# efm8ub1-kalypso-mezzanine-usb-interface-.net
KiCad netlist of a schematic drawn in EAGLE
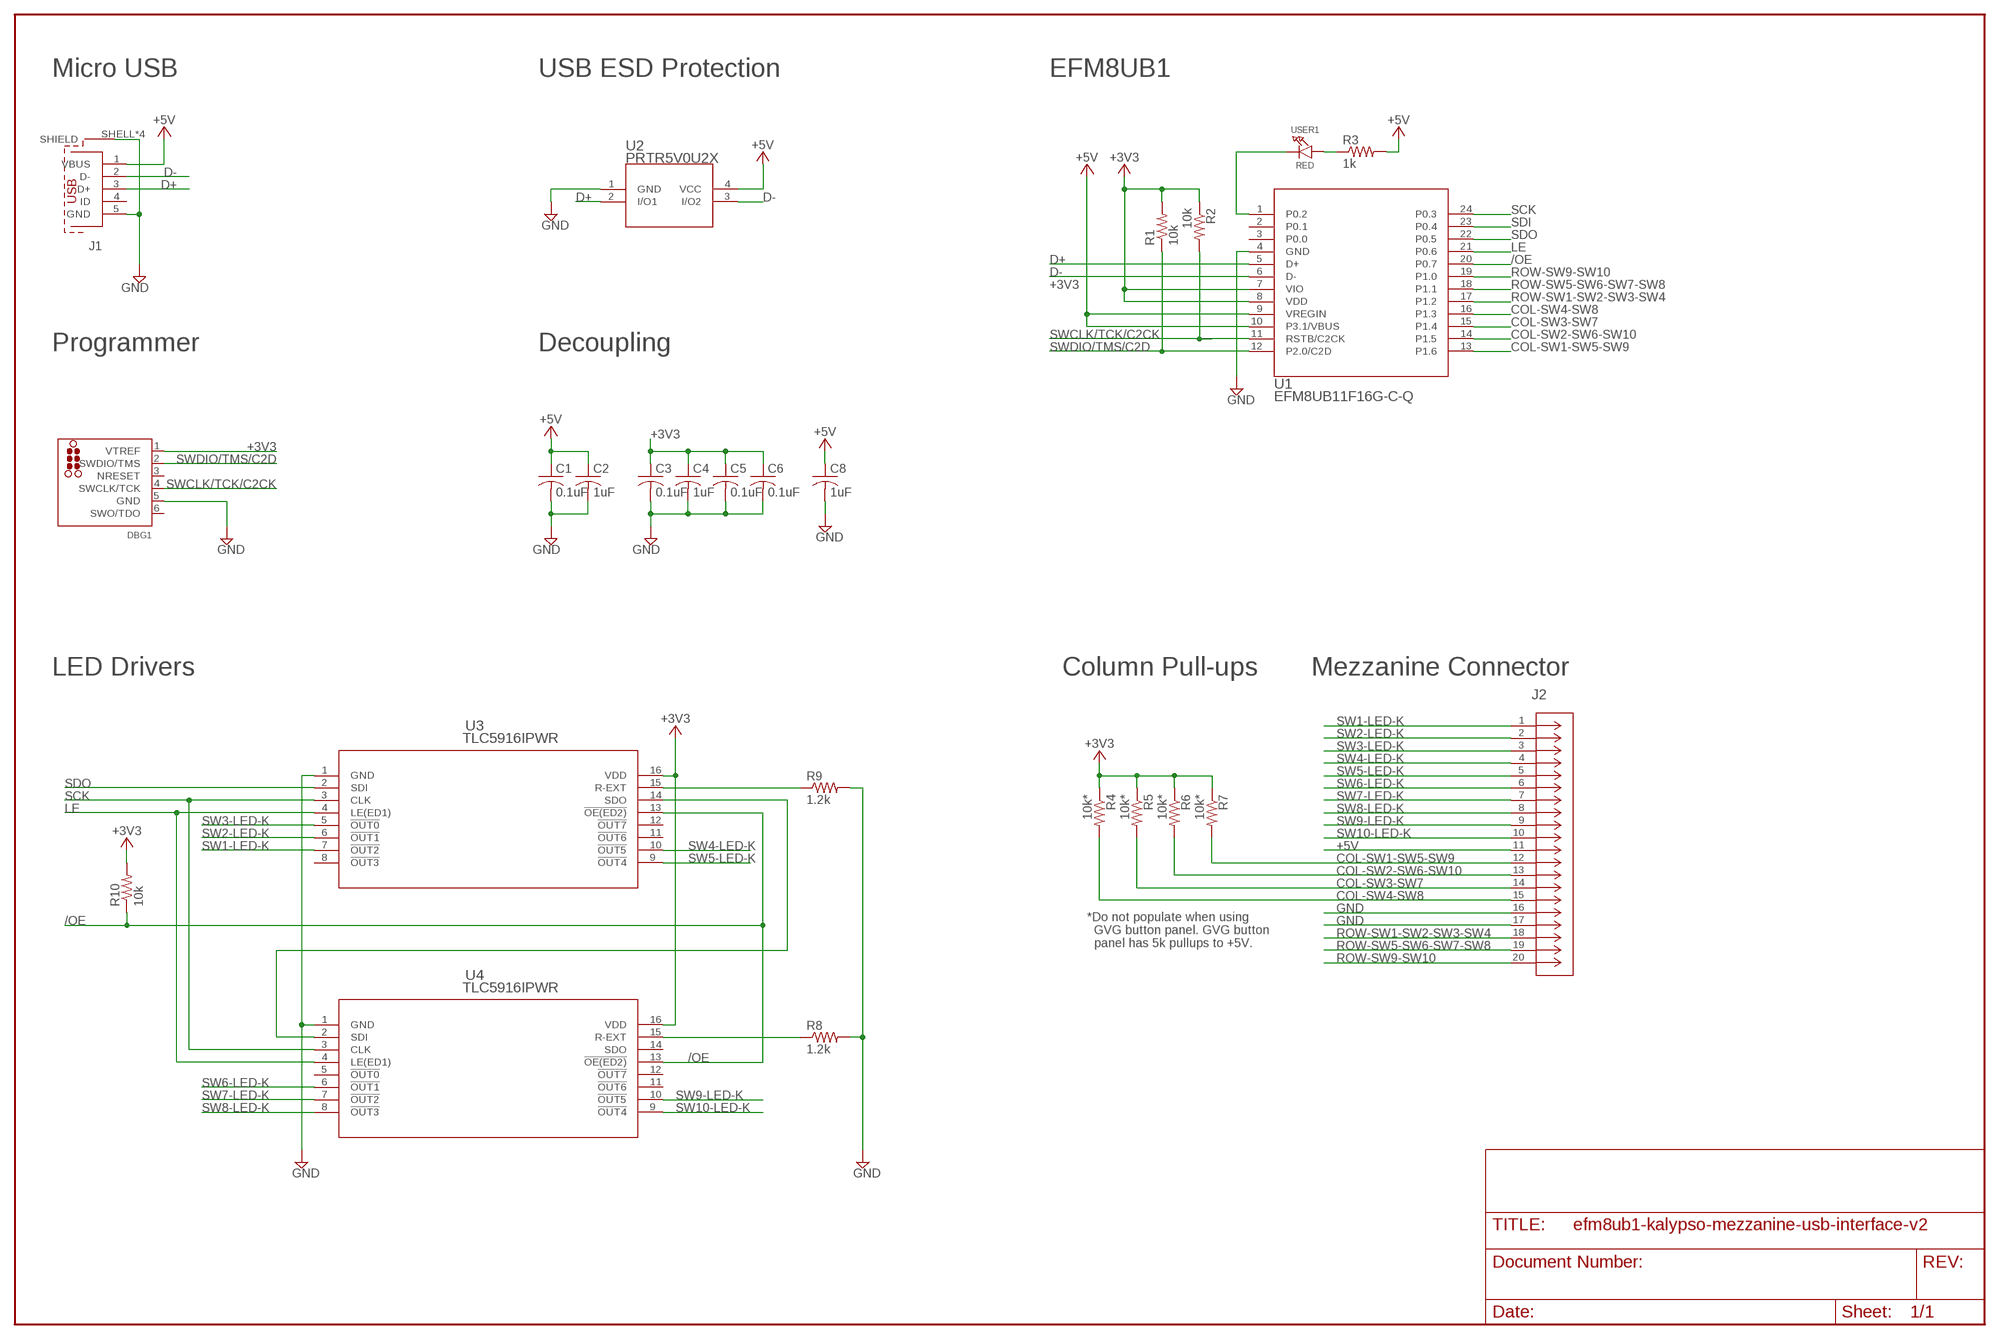
[diagram p0: schematic, sheet 1]

(export (version "E")
  (design (tool "Eeschema 10.0.6"))
  (components
    (comp (ref "C1")
      (value "0.1uF")
      (footprint "eagle-import:C0603")
      (libsource (lib "eagle-import") (part "C-USC0603"))
    )
    (comp (ref "C2")
      (value "1uF")
      (footprint "eagle-import:C0603")
      (libsource (lib "eagle-import") (part "C-USC0603"))
    )
    (comp (ref "C3")
      (value "0.1uF")
      (footprint "eagle-import:C0603")
      (libsource (lib "eagle-import") (part "C-USC0603"))
    )
    (comp (ref "C4")
      (value "1uF")
      (footprint "eagle-import:C0603")
      (libsource (lib "eagle-import") (part "C-USC0603"))
    )
    (comp (ref "C5")
      (value "0.1uF")
      (footprint "eagle-import:C0603")
      (libsource (lib "eagle-import") (part "C-USC0603"))
    )
    (comp (ref "C6")
      (value "0.1uF")
      (footprint "eagle-import:C0603")
      (libsource (lib "eagle-import") (part "C-USC0603"))
    )
    (comp (ref "C8")
      (value "1uF")
      (footprint "eagle-import:C1210")
      (libsource (lib "eagle-import") (part "C-USC1210"))
    )
    (comp (ref "DBG1")
      (value "TC2030-CTX-SWD")
      (footprint "eagle-import:TC2030-MCP-NL")
      (libsource (lib "eagle-import") (part "TC2030-CTX-SWD"))
    )
    (comp (ref "J1")
      (value "629105136821")
      (footprint "eagle-import:629105136821")
      (libsource (lib "eagle-import") (part "629105136821"))
    )
    (comp (ref "J2")
      (value "SLW20S-1C7LF")
      (footprint "eagle-import:CON20_1X20_UB_58JF_GLE")
      (libsource (lib "eagle-import") (part "SLW20S-1C7LF"))
    )
    (comp (ref "R1")
      (value "10k")
      (footprint "eagle-import:R0603")
      (libsource (lib "eagle-import") (part "R-US_R0603"))
    )
    (comp (ref "R2")
      (value "10k")
      (footprint "eagle-import:R0603")
      (libsource (lib "eagle-import") (part "R-US_R0603"))
    )
    (comp (ref "R3")
      (value "1k")
      (footprint "eagle-import:R0603")
      (libsource (lib "eagle-import") (part "R-US_R0603"))
    )
    (comp (ref "R4")
      (value "10k*")
      (footprint "eagle-import:R0603")
      (libsource (lib "eagle-import") (part "R-US_R0603"))
    )
    (comp (ref "R5")
      (value "10k*")
      (footprint "eagle-import:R0603")
      (libsource (lib "eagle-import") (part "R-US_R0603"))
    )
    (comp (ref "R6")
      (value "10k*")
      (footprint "eagle-import:R0603")
      (libsource (lib "eagle-import") (part "R-US_R0603"))
    )
    (comp (ref "R7")
      (value "10k*")
      (footprint "eagle-import:R0603")
      (libsource (lib "eagle-import") (part "R-US_R0603"))
    )
    (comp (ref "R8")
      (value "1.2k")
      (footprint "eagle-import:R0603")
      (libsource (lib "eagle-import") (part "R-US_R0603"))
    )
    (comp (ref "R9")
      (value "1.2k")
      (footprint "eagle-import:R0603")
      (libsource (lib "eagle-import") (part "R-US_R0603"))
    )
    (comp (ref "R10")
      (value "10k")
      (footprint "eagle-import:R0603")
      (libsource (lib "eagle-import") (part "R-US_R0603"))
    )
    (comp (ref "U1")
      (value "EFM8UB11F16G-C-Q")
      (footprint "eagle-import:QSOP24")
      (fields (field (name "MANUFACTURER_PART_NUMBER") "efm8ub11f16gbqsop24"))
      (libsource (lib "eagle-import") (part "EFM8UB11F16G-C-Q"))
    )
    (comp (ref "U2")
      (value "PRTR5V0U2X")
      (footprint "eagle-import:SOT143B")
      (libsource (lib "eagle-import") (part "PRTR5V0U2X"))
    )
    (comp (ref "U3")
      (value "TLC5916IPWR")
      (footprint "eagle-import:PW16_TEX")
      (fields (field (name "MANUFACTURER") "Texas Instruments"))
      (libsource (lib "eagle-import") (part "TLC5916IPWR"))
    )
    (comp (ref "U4")
      (value "TLC5916IPWR")
      (footprint "eagle-import:PW16_TEX")
      (fields (field (name "MANUFACTURER") "Texas Instruments"))
      (libsource (lib "eagle-import") (part "TLC5916IPWR"))
    )
    (comp (ref "USER1")
      (value "RED")
      (footprint "eagle-import:CHIPLED_0805_NOOUTLINE")
      (libsource (lib "eagle-import") (part "LED0805_NOOUTLINE"))
    )
  )
  (nets
    (net (code "1") (name "+3V3") (class "Default")
      (node (ref "C3") (pin "1") (pinfunction "1_1") (pintype "passive"))
      (node (ref "C4") (pin "1") (pinfunction "1_1") (pintype "passive"))
      (node (ref "C5") (pin "1") (pinfunction "1_1") (pintype "passive"))
      (node (ref "C6") (pin "1") (pinfunction "1_1") (pintype "passive"))
      (node (ref "DBG1") (pin "1") (pinfunction "VTREF_1") (pintype "passive"))
      (node (ref "R1") (pin "2") (pinfunction "2_2") (pintype "passive"))
      (node (ref "R10") (pin "2") (pinfunction "2_2") (pintype "passive"))
      (node (ref "R2") (pin "1") (pinfunction "1_1") (pintype "passive"))
      (node (ref "R4") (pin "1") (pinfunction "1_1") (pintype "passive"))
      (node (ref "R5") (pin "1") (pinfunction "1_1") (pintype "passive"))
      (node (ref "R6") (pin "1") (pinfunction "1_1") (pintype "passive"))
      (node (ref "R7") (pin "1") (pinfunction "1_1") (pintype "passive"))
      (node (ref "U1") (pin "7") (pinfunction "VIO_7") (pintype "bidirectional"))
      (node (ref "U1") (pin "8") (pinfunction "VDD_8") (pintype "power_in"))
      (node (ref "U3") (pin "16") (pinfunction "VDD_16") (pintype "power_in"))
      (node (ref "U4") (pin "16") (pinfunction "VDD_16") (pintype "power_in"))
    )
    (net (code "2") (name "+5V") (class "Default")
      (node (ref "C1") (pin "1") (pinfunction "1_1") (pintype "passive"))
      (node (ref "C2") (pin "1") (pinfunction "1_1") (pintype "passive"))
      (node (ref "C8") (pin "1") (pinfunction "1_1") (pintype "passive"))
      (node (ref "J1") (pin "1") (pinfunction "VBUS_1") (pintype "passive"))
      (node (ref "J2") (pin "11") (pinfunction "11_11") (pintype "passive"))
      (node (ref "R3") (pin "2") (pinfunction "2_2") (pintype "passive"))
      (node (ref "U1") (pin "10") (pinfunction "P3.1/VBUS_10") (pintype "bidirectional"))
      (node (ref "U1") (pin "9") (pinfunction "VREGIN_9") (pintype "input"))
      (node (ref "U2") (pin "4") (pinfunction "VCC_4") (pintype "passive"))
    )
    (net (code "3") (name "/COL-SW1-SW5-SW9") (class "Default")
      (node (ref "J2") (pin "12") (pinfunction "12_12") (pintype "passive"))
      (node (ref "R7") (pin "2") (pinfunction "2_2") (pintype "passive"))
      (node (ref "U1") (pin "13") (pinfunction "P1.6_13") (pintype "bidirectional"))
    )
    (net (code "4") (name "/COL-SW2-SW6-SW10") (class "Default")
      (node (ref "J2") (pin "13") (pinfunction "13_13") (pintype "passive"))
      (node (ref "R6") (pin "2") (pinfunction "2_2") (pintype "passive"))
      (node (ref "U1") (pin "14") (pinfunction "P1.5_14") (pintype "bidirectional"))
    )
    (net (code "5") (name "/COL-SW3-SW7") (class "Default")
      (node (ref "J2") (pin "14") (pinfunction "14_14") (pintype "passive"))
      (node (ref "R5") (pin "2") (pinfunction "2_2") (pintype "passive"))
      (node (ref "U1") (pin "15") (pinfunction "P1.4_15") (pintype "bidirectional"))
    )
    (net (code "6") (name "/COL-SW4-SW8") (class "Default")
      (node (ref "J2") (pin "15") (pinfunction "15_15") (pintype "passive"))
      (node (ref "R4") (pin "2") (pinfunction "2_2") (pintype "passive"))
      (node (ref "U1") (pin "16") (pinfunction "P1.3_16") (pintype "bidirectional"))
    )
    (net (code "7") (name "/D+") (class "Default")
      (node (ref "J1") (pin "3") (pinfunction "D+_3") (pintype "passive"))
      (node (ref "U1") (pin "5") (pinfunction "D+_5") (pintype "bidirectional"))
      (node (ref "U2") (pin "2") (pinfunction "I/O1_2") (pintype "passive"))
    )
    (net (code "8") (name "/D-") (class "Default")
      (node (ref "J1") (pin "2") (pinfunction "D-_2") (pintype "passive"))
      (node (ref "U1") (pin "6") (pinfunction "D-_6") (pintype "bidirectional"))
      (node (ref "U2") (pin "3") (pinfunction "I/O2_3") (pintype "passive"))
    )
    (net (code "9") (name "/LE") (class "Default")
      (node (ref "U1") (pin "21") (pinfunction "P0.6_21") (pintype "bidirectional"))
      (node (ref "U3") (pin "4") (pinfunction "LE(ED1)_4") (pintype "input"))
      (node (ref "U4") (pin "4") (pinfunction "LE(ED1)_4") (pintype "input"))
    )
    (net (code "10") (name "/NRESET") (class "Default")
      (node (ref "DBG1") (pin "3") (pinfunction "NRESET_3") (pintype "power_in"))
    )
    (net (code "11") (name "/ROW-SW1-SW2-SW3-SW4") (class "Default")
      (node (ref "J2") (pin "18") (pinfunction "18_18") (pintype "passive"))
      (node (ref "U1") (pin "17") (pinfunction "P1.2_17") (pintype "bidirectional"))
    )
    (net (code "12") (name "/ROW-SW5-SW6-SW7-SW8") (class "Default")
      (node (ref "J2") (pin "19") (pinfunction "19_19") (pintype "passive"))
      (node (ref "U1") (pin "18") (pinfunction "P1.1_18") (pintype "bidirectional"))
    )
    (net (code "13") (name "/ROW-SW9-SW10") (class "Default")
      (node (ref "J2") (pin "20") (pinfunction "20_20") (pintype "passive"))
      (node (ref "U1") (pin "19") (pinfunction "P1.0_19") (pintype "bidirectional"))
    )
    (net (code "14") (name "/SCK") (class "Default")
      (node (ref "U1") (pin "24") (pinfunction "P0.3_24") (pintype "bidirectional"))
      (node (ref "U3") (pin "3") (pinfunction "CLK_3") (pintype "input"))
      (node (ref "U4") (pin "3") (pinfunction "CLK_3") (pintype "input"))
    )
    (net (code "15") (name "/SDI") (class "Default")
      (node (ref "U1") (pin "23") (pinfunction "P0.4_23") (pintype "bidirectional"))
    )
    (net (code "16") (name "/SDO") (class "Default")
      (node (ref "U1") (pin "22") (pinfunction "P0.5_22") (pintype "bidirectional"))
      (node (ref "U3") (pin "2") (pinfunction "SDI_2") (pintype "input"))
    )
    (net (code "17") (name "/SW1-LED-K") (class "Default")
      (node (ref "J2") (pin "1") (pinfunction "1_1") (pintype "passive"))
      (node (ref "U3") (pin "7") (pinfunction "~{OUT2}_7") (pintype "output"))
    )
    (net (code "18") (name "/SW2-LED-K") (class "Default")
      (node (ref "J2") (pin "2") (pinfunction "2_2") (pintype "passive"))
      (node (ref "U3") (pin "6") (pinfunction "~{OUT1}_6") (pintype "output"))
    )
    (net (code "19") (name "/SW3-LED-K") (class "Default")
      (node (ref "J2") (pin "3") (pinfunction "3_3") (pintype "passive"))
      (node (ref "U3") (pin "5") (pinfunction "~{OUT0}_5") (pintype "output"))
    )
    (net (code "20") (name "/SW4-LED-K") (class "Default")
      (node (ref "J2") (pin "4") (pinfunction "4_4") (pintype "passive"))
      (node (ref "U3") (pin "10") (pinfunction "~{OUT5}_10") (pintype "output"))
    )
    (net (code "21") (name "/SW5-LED-K") (class "Default")
      (node (ref "J2") (pin "5") (pinfunction "5_5") (pintype "passive"))
      (node (ref "U3") (pin "9") (pinfunction "~{OUT4}_9") (pintype "output"))
    )
    (net (code "22") (name "/SW6-LED-K") (class "Default")
      (node (ref "J2") (pin "6") (pinfunction "6_6") (pintype "passive"))
      (node (ref "U4") (pin "6") (pinfunction "~{OUT1}_6") (pintype "output"))
    )
    (net (code "23") (name "/SW7-LED-K") (class "Default")
      (node (ref "J2") (pin "7") (pinfunction "7_7") (pintype "passive"))
      (node (ref "U4") (pin "7") (pinfunction "~{OUT2}_7") (pintype "output"))
    )
    (net (code "24") (name "/SW8-LED-K") (class "Default")
      (node (ref "J2") (pin "8") (pinfunction "8_8") (pintype "passive"))
      (node (ref "U4") (pin "8") (pinfunction "~{OUT3}_8") (pintype "output"))
    )
    (net (code "25") (name "/SW9-LED-K") (class "Default")
      (node (ref "J2") (pin "9") (pinfunction "9_9") (pintype "passive"))
      (node (ref "U4") (pin "10") (pinfunction "~{OUT5}_10") (pintype "output"))
    )
    (net (code "26") (name "/SW10-LED-K") (class "Default")
      (node (ref "J2") (pin "10") (pinfunction "10_10") (pintype "passive"))
      (node (ref "U4") (pin "9") (pinfunction "~{OUT4}_9") (pintype "output"))
    )
    (net (code "27") (name "/SWCLK{slash}TCK{slash}C2CK") (class "Default")
      (node (ref "DBG1") (pin "4") (pinfunction "SWCLK/TCK_4") (pintype "bidirectional"))
      (node (ref "R2") (pin "2") (pinfunction "2_2") (pintype "passive"))
      (node (ref "U1") (pin "11") (pinfunction "RSTB/C2CK_11") (pintype "bidirectional"))
    )
    (net (code "28") (name "/SWDIO{slash}TMS{slash}C2D") (class "Default")
      (node (ref "DBG1") (pin "2") (pinfunction "SWDIO/TMS_2") (pintype "power_in"))
      (node (ref "R1") (pin "1") (pinfunction "1_1") (pintype "passive"))
      (node (ref "U1") (pin "12") (pinfunction "P2.0/C2D_12") (pintype "bidirectional"))
    )
    (net (code "29") (name "/{slash}OE") (class "Default")
      (node (ref "R10") (pin "1") (pinfunction "1_1") (pintype "passive"))
      (node (ref "U1") (pin "20") (pinfunction "P0.7_20") (pintype "bidirectional"))
      (node (ref "U3") (pin "13") (pinfunction "~{OE(ED2})_13") (pintype "output"))
      (node (ref "U4") (pin "13") (pinfunction "~{OE(ED2})_13") (pintype "output"))
    )
    (net (code "30") (name "GND") (class "Default")
      (node (ref "C1") (pin "2") (pinfunction "2_2") (pintype "passive"))
      (node (ref "C2") (pin "2") (pinfunction "2_2") (pintype "passive"))
      (node (ref "C3") (pin "2") (pinfunction "2_2") (pintype "passive"))
      (node (ref "C4") (pin "2") (pinfunction "2_2") (pintype "passive"))
      (node (ref "C5") (pin "2") (pinfunction "2_2") (pintype "passive"))
      (node (ref "C6") (pin "2") (pinfunction "2_2") (pintype "passive"))
      (node (ref "C8") (pin "2") (pinfunction "2_2") (pintype "passive"))
      (node (ref "DBG1") (pin "5") (pinfunction "GND_5") (pintype "output"))
      (node (ref "J1") (pin "5") (pinfunction "GND_5") (pintype "passive"))
      (node (ref "J1") (pin "SHELL") (pinfunction "SHIELD_SHELL") (pintype "passive"))
      (node (ref "J1") (pin "SHELL1") (pinfunction "SHIELD_SHELL1") (pintype "passive"))
      (node (ref "J1") (pin "SHELL2") (pinfunction "SHIELD_SHELL2") (pintype "passive"))
      (node (ref "J1") (pin "SHELL3") (pinfunction "SHIELD_SHELL3") (pintype "passive"))
      (node (ref "J2") (pin "16") (pinfunction "16_16") (pintype "passive"))
      (node (ref "J2") (pin "17") (pinfunction "17_17") (pintype "passive"))
      (node (ref "R8") (pin "2") (pinfunction "2_2") (pintype "passive"))
      (node (ref "R9") (pin "2") (pinfunction "2_2") (pintype "passive"))
      (node (ref "U1") (pin "4") (pinfunction "GND_4") (pintype "power_in"))
      (node (ref "U2") (pin "1") (pinfunction "GND_1") (pintype "passive"))
      (node (ref "U3") (pin "1") (pinfunction "GND_1") (pintype "power_in"))
      (node (ref "U4") (pin "1") (pinfunction "GND_1") (pintype "power_in"))
    )
    (net (code "31") (name "Net-(R3-Pad1)") (class "Default")
      (node (ref "R3") (pin "1") (pinfunction "1_1") (pintype "passive"))
      (node (ref "USER1") (pin "A") (pinfunction "A_A") (pintype "passive"))
    )
    (net (code "32") (name "Net-(U1-P0.2)") (class "Default")
      (node (ref "U1") (pin "1") (pinfunction "P0.2_1") (pintype "bidirectional"))
      (node (ref "USER1") (pin "C") (pinfunction "C_C") (pintype "passive"))
    )
    (net (code "33") (name "Net-(U3-R-EXT)") (class "Default")
      (node (ref "R9") (pin "1") (pinfunction "1_1") (pintype "passive"))
      (node (ref "U3") (pin "15") (pinfunction "R-EXT_15") (pintype "passive"))
    )
    (net (code "34") (name "Net-(U3-SDO)") (class "Default")
      (node (ref "U3") (pin "14") (pinfunction "SDO_14") (pintype "output"))
      (node (ref "U4") (pin "2") (pinfunction "SDI_2") (pintype "input"))
    )
    (net (code "35") (name "Net-(U4-R-EXT)") (class "Default")
      (node (ref "R8") (pin "1") (pinfunction "1_1") (pintype "passive"))
      (node (ref "U4") (pin "15") (pinfunction "R-EXT_15") (pintype "passive"))
    )
    (net (code "36") (name "unconnected-(DBG1-SWO{slash}TDO-Pad6)") (class "Default")
      (node (ref "DBG1") (pin "6") (pinfunction "SWO/TDO_6") (pintype "bidirectional"))
    )
    (net (code "37") (name "unconnected-(J1-ID-Pad4)") (class "Default")
      (node (ref "J1") (pin "4") (pinfunction "ID_4") (pintype "passive"))
    )
    (net (code "38") (name "unconnected-(U1-P0.0-Pad3)") (class "Default")
      (node (ref "U1") (pin "3") (pinfunction "P0.0_3") (pintype "bidirectional"))
    )
    (net (code "39") (name "unconnected-(U1-P0.1-Pad2)") (class "Default")
      (node (ref "U1") (pin "2") (pinfunction "P0.1_2") (pintype "bidirectional"))
    )
    (net (code "40") (name "unconnected-(U3-~{OUT3}-Pad8)") (class "Default")
      (node (ref "U3") (pin "8") (pinfunction "~{OUT3}_8") (pintype "output"))
    )
    (net (code "41") (name "unconnected-(U3-~{OUT6}-Pad11)") (class "Default")
      (node (ref "U3") (pin "11") (pinfunction "~{OUT6}_11") (pintype "output"))
    )
    (net (code "42") (name "unconnected-(U3-~{OUT7}-Pad12)") (class "Default")
      (node (ref "U3") (pin "12") (pinfunction "~{OUT7}_12") (pintype "output"))
    )
    (net (code "43") (name "unconnected-(U4-SDO-Pad14)") (class "Default")
      (node (ref "U4") (pin "14") (pinfunction "SDO_14") (pintype "output"))
    )
    (net (code "44") (name "unconnected-(U4-~{OUT0}-Pad5)") (class "Default")
      (node (ref "U4") (pin "5") (pinfunction "~{OUT0}_5") (pintype "output"))
    )
    (net (code "45") (name "unconnected-(U4-~{OUT6}-Pad11)") (class "Default")
      (node (ref "U4") (pin "11") (pinfunction "~{OUT6}_11") (pintype "output"))
    )
    (net (code "46") (name "unconnected-(U4-~{OUT7}-Pad12)") (class "Default")
      (node (ref "U4") (pin "12") (pinfunction "~{OUT7}_12") (pintype "output"))
    )
  )
)
